# simpleOscOne3.net
KiCad netlist of a schematic drawn in EAGLE
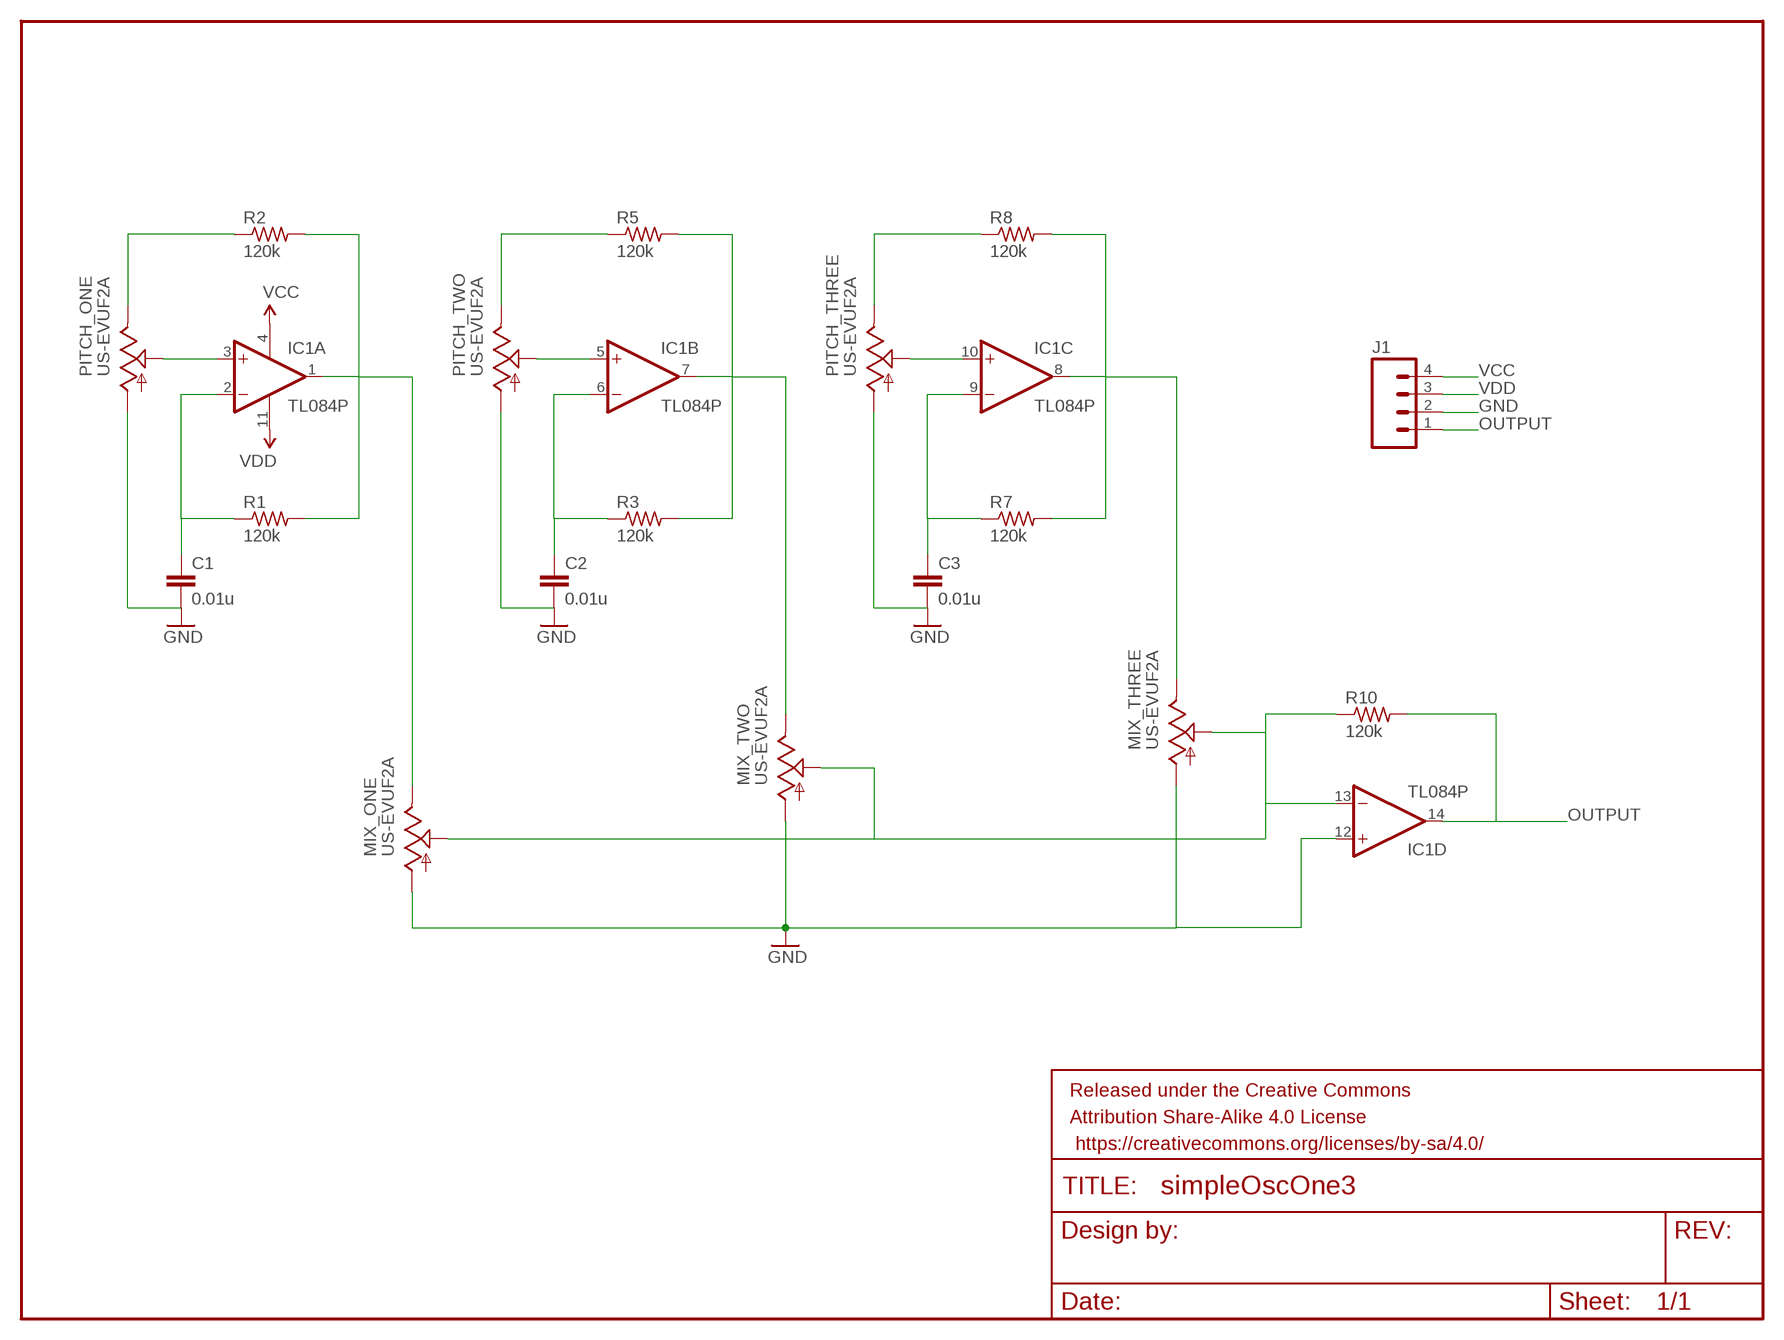
[diagram p0: schematic, sheet 1]

(export (version "E")
  (design (tool "Eeschema 10.0.6"))
  (components
    (comp (ref "C1")
      (value "0.01u")
      (footprint "eagle-import:AXIAL-5MM")
      (libsource (lib "eagle-import") (part "CAP_"))
    )
    (comp (ref "C2")
      (value "0.01u")
      (footprint "eagle-import:AXIAL-5MM")
      (libsource (lib "eagle-import") (part "CAP_"))
    )
    (comp (ref "C3")
      (value "0.01u")
      (footprint "eagle-import:AXIAL-5MM")
      (libsource (lib "eagle-import") (part "CAP_"))
    )
    (comp (ref "FRAME1")
      (value "FRAME-LETTERNO_PACKAGE")
      (footprint "eagle-import:DUMMY")
      (fields (field (name "DESIGNER") "Nobody"))
      (libsource (lib "eagle-import") (part "FRAME-LETTERNO_PACKAGE"))
    )
    (comp (ref "IC1")
      (value "TL084P")
      (footprint "eagle-import:DIL14")
      (libsource (lib "eagle-import") (part "TL084P"))
    )
    (comp (ref "J1")
      (value "M04NO_SILK_ALL_ROUND")
      (footprint "eagle-import:1X04_NO_SILK_ALL_ROUND")
      (libsource (lib "eagle-import") (part "M04NO_SILK_ALL_ROUND"))
    )
    (comp (ref "MIX_ONE")
      (value "US-EVUF2A")
      (footprint "eagle-import:EVUF")
      (libsource (lib "eagle-import") (part "US-EVUAF2"))
    )
    (comp (ref "MIX_THREE")
      (value "US-EVUF2A")
      (footprint "eagle-import:EVUF")
      (libsource (lib "eagle-import") (part "US-EVUAF2"))
    )
    (comp (ref "MIX_TWO")
      (value "US-EVUF2A")
      (footprint "eagle-import:EVUF")
      (libsource (lib "eagle-import") (part "US-EVUAF2"))
    )
    (comp (ref "PITCH_ONE")
      (value "US-EVUF2A")
      (footprint "eagle-import:EVUF")
      (libsource (lib "eagle-import") (part "US-EVUAF2"))
    )
    (comp (ref "PITCH_THREE")
      (value "US-EVUF2A")
      (footprint "eagle-import:EVUF")
      (libsource (lib "eagle-import") (part "US-EVUAF2"))
    )
    (comp (ref "PITCH_TWO")
      (value "US-EVUF2A")
      (footprint "eagle-import:EVUF")
      (libsource (lib "eagle-import") (part "US-EVUAF2"))
    )
    (comp (ref "R1")
      (value "120k")
      (footprint "eagle-import:0204_7")
      (libsource (lib "eagle-import") (part "R-US_0204/7"))
    )
    (comp (ref "R2")
      (value "120k")
      (footprint "eagle-import:0204_7")
      (libsource (lib "eagle-import") (part "R-US_0204/7"))
    )
    (comp (ref "R3")
      (value "120k")
      (footprint "eagle-import:0204_7")
      (libsource (lib "eagle-import") (part "R-US_0204/7"))
    )
    (comp (ref "R5")
      (value "120k")
      (footprint "eagle-import:0204_7")
      (libsource (lib "eagle-import") (part "R-US_0204/7"))
    )
    (comp (ref "R7")
      (value "120k")
      (footprint "eagle-import:0204_7")
      (libsource (lib "eagle-import") (part "R-US_0204/7"))
    )
    (comp (ref "R8")
      (value "120k")
      (footprint "eagle-import:0204_7")
      (libsource (lib "eagle-import") (part "R-US_0204/7"))
    )
    (comp (ref "R10")
      (value "120k")
      (footprint "eagle-import:0204_7")
      (libsource (lib "eagle-import") (part "R-US_0204/7"))
    )
  )
  (nets
    (net (code "1") (name "/OUTPUT") (class "Default")
      (node (ref "IC1") (pin "14") (pinfunction "OUT_14") (pintype "output"))
      (node (ref "J1") (pin "1") (pinfunction "1_1") (pintype "passive"))
      (node (ref "R10") (pin "2") (pinfunction "2_2") (pintype "passive"))
    )
    (net (code "2") (name "GND") (class "Default")
      (node (ref "C1") (pin "P$2") (pinfunction "2_P$2") (pintype "passive"))
      (node (ref "C2") (pin "P$2") (pinfunction "2_P$2") (pintype "passive"))
      (node (ref "C3") (pin "P$2") (pinfunction "2_P$2") (pintype "passive"))
      (node (ref "IC1") (pin "12") (pinfunction "+IN_12") (pintype "input"))
      (node (ref "J1") (pin "2") (pinfunction "2_2") (pintype "passive"))
      (node (ref "MIX_ONE") (pin "1") (pinfunction "A_1") (pintype "passive"))
      (node (ref "MIX_THREE") (pin "1") (pinfunction "A_1") (pintype "passive"))
      (node (ref "MIX_TWO") (pin "1") (pinfunction "A_1") (pintype "passive"))
      (node (ref "PITCH_ONE") (pin "1") (pinfunction "A_1") (pintype "passive"))
      (node (ref "PITCH_THREE") (pin "1") (pinfunction "A_1") (pintype "passive"))
      (node (ref "PITCH_TWO") (pin "1") (pinfunction "A_1") (pintype "passive"))
    )
    (net (code "3") (name "Net-(C1-1)") (class "Default")
      (node (ref "C1") (pin "P$1") (pinfunction "1_P$1") (pintype "passive"))
      (node (ref "IC1") (pin "2") (pinfunction "-IN_2") (pintype "input"))
      (node (ref "R1") (pin "1") (pinfunction "1_1") (pintype "passive"))
    )
    (net (code "4") (name "Net-(C2-1)") (class "Default")
      (node (ref "C2") (pin "P$1") (pinfunction "1_P$1") (pintype "passive"))
      (node (ref "IC1") (pin "6") (pinfunction "-IN_6") (pintype "input"))
      (node (ref "R3") (pin "1") (pinfunction "1_1") (pintype "passive"))
    )
    (net (code "5") (name "Net-(C3-1)") (class "Default")
      (node (ref "C3") (pin "P$1") (pinfunction "1_P$1") (pintype "passive"))
      (node (ref "IC1") (pin "9") (pinfunction "-IN_9") (pintype "input"))
      (node (ref "R7") (pin "1") (pinfunction "1_1") (pintype "passive"))
    )
    (net (code "6") (name "Net-(IC1A-+IN)") (class "Default")
      (node (ref "IC1") (pin "3") (pinfunction "+IN_3") (pintype "input"))
      (node (ref "PITCH_ONE") (pin "2") (pinfunction "S_2") (pintype "passive"))
    )
    (net (code "7") (name "Net-(IC1A-OUT)") (class "Default")
      (node (ref "IC1") (pin "1") (pinfunction "OUT_1") (pintype "output"))
      (node (ref "MIX_ONE") (pin "3") (pinfunction "E_3") (pintype "passive"))
      (node (ref "R1") (pin "2") (pinfunction "2_2") (pintype "passive"))
      (node (ref "R2") (pin "2") (pinfunction "2_2") (pintype "passive"))
    )
    (net (code "8") (name "Net-(IC1B-+IN)") (class "Default")
      (node (ref "IC1") (pin "5") (pinfunction "+IN_5") (pintype "input"))
      (node (ref "PITCH_TWO") (pin "2") (pinfunction "S_2") (pintype "passive"))
    )
    (net (code "9") (name "Net-(IC1B-OUT)") (class "Default")
      (node (ref "IC1") (pin "7") (pinfunction "OUT_7") (pintype "output"))
      (node (ref "MIX_TWO") (pin "3") (pinfunction "E_3") (pintype "passive"))
      (node (ref "R3") (pin "2") (pinfunction "2_2") (pintype "passive"))
      (node (ref "R5") (pin "2") (pinfunction "2_2") (pintype "passive"))
    )
    (net (code "10") (name "Net-(IC1C-+IN)") (class "Default")
      (node (ref "IC1") (pin "10") (pinfunction "+IN_10") (pintype "input"))
      (node (ref "PITCH_THREE") (pin "2") (pinfunction "S_2") (pintype "passive"))
    )
    (net (code "11") (name "Net-(IC1C-OUT)") (class "Default")
      (node (ref "IC1") (pin "8") (pinfunction "OUT_8") (pintype "output"))
      (node (ref "MIX_THREE") (pin "3") (pinfunction "E_3") (pintype "passive"))
      (node (ref "R7") (pin "2") (pinfunction "2_2") (pintype "passive"))
      (node (ref "R8") (pin "2") (pinfunction "2_2") (pintype "passive"))
    )
    (net (code "12") (name "Net-(IC1D--IN)") (class "Default")
      (node (ref "IC1") (pin "13") (pinfunction "-IN_13") (pintype "input"))
      (node (ref "MIX_ONE") (pin "2") (pinfunction "S_2") (pintype "passive"))
      (node (ref "MIX_THREE") (pin "2") (pinfunction "S_2") (pintype "passive"))
      (node (ref "MIX_TWO") (pin "2") (pinfunction "S_2") (pintype "passive"))
      (node (ref "R10") (pin "1") (pinfunction "1_1") (pintype "passive"))
    )
    (net (code "13") (name "Net-(PITCH_ONE-E)") (class "Default")
      (node (ref "PITCH_ONE") (pin "3") (pinfunction "E_3") (pintype "passive"))
      (node (ref "R2") (pin "1") (pinfunction "1_1") (pintype "passive"))
    )
    (net (code "14") (name "Net-(PITCH_THREE-E)") (class "Default")
      (node (ref "PITCH_THREE") (pin "3") (pinfunction "E_3") (pintype "passive"))
      (node (ref "R8") (pin "1") (pinfunction "1_1") (pintype "passive"))
    )
    (net (code "15") (name "Net-(PITCH_TWO-E)") (class "Default")
      (node (ref "PITCH_TWO") (pin "3") (pinfunction "E_3") (pintype "passive"))
      (node (ref "R5") (pin "1") (pinfunction "1_1") (pintype "passive"))
    )
    (net (code "16") (name "VCC") (class "Default")
      (node (ref "IC1") (pin "4") (pinfunction "V+_4") (pintype "power_in"))
      (node (ref "J1") (pin "4") (pinfunction "4_4") (pintype "passive"))
    )
    (net (code "17") (name "VDD") (class "Default")
      (node (ref "IC1") (pin "11") (pinfunction "V-_11") (pintype "power_in"))
      (node (ref "J1") (pin "3") (pinfunction "3_3") (pintype "passive"))
    )
  )
)
